# Sheet2.net
KiCad netlist of a schematic drawn in Altium Designer
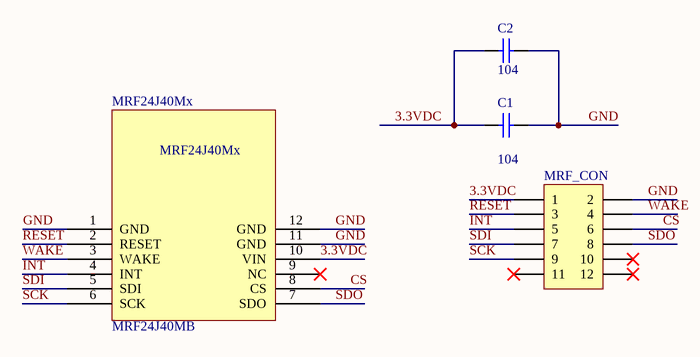
[diagram p0: Sheet2.SchDoc]

(export (version "E")
  (design (tool "Eeschema 10.0.6"))
  (components
    (comp (ref "C1")
      (value "104")
      (footprint "CN1.5")
      (description "Capacitor")
      (fields (field (name "Comment") "Cap") (field (name "PUBLISHER") "Altium Limited"))
      (libsource (lib "Miscellaneous Devices") (part "Cap"))
    )
    (comp (ref "C2")
      (value "104")
      (footprint "CN1.5")
      (description "Capacitor")
      (fields (field (name "Comment") "Cap") (field (name "PUBLISHER") "Altium Limited"))
      (libsource (lib "Miscellaneous Devices") (part "Cap"))
    )
    (comp (ref "MRF24J40Mx")
      (value "MRF24J40MB")
      (footprint "MRF24J40MB")
      (libsource (lib "syhaunguyen") (part "MRF24J40MB"))
    )
    (comp (ref "MRF_CON")
      (value "Header 6X2")
      (footprint "HDR2X6")
      (description "Header, 6-Pin, Dual row")
      (fields (field (name "PUBLISHER") "Altium Limited"))
      (libsource (lib "Miscellaneous Connectors") (part "Header 6X2"))
    )
  )
  (nets
    (net (code "1") (name "/3.3VDC") (class "Default")
      (node (ref "C1") (pin "2") (pinfunction "2_2") (pintype "passive"))
      (node (ref "C2") (pin "1") (pinfunction "1_1") (pintype "passive"))
      (node (ref "MRF24J40Mx") (pin "10") (pinfunction "VIN_10") (pintype "passive"))
      (node (ref "MRF_CON") (pin "1") (pinfunction "1_1") (pintype "passive"))
    )
    (net (code "2") (name "/CS") (class "Default")
      (node (ref "MRF24J40Mx") (pin "8") (pinfunction "CS_8") (pintype "passive"))
      (node (ref "MRF_CON") (pin "6") (pinfunction "6_6") (pintype "passive"))
    )
    (net (code "3") (name "/GND") (class "Default")
      (node (ref "C1") (pin "1") (pinfunction "1_1") (pintype "passive"))
      (node (ref "C2") (pin "2") (pinfunction "2_2") (pintype "passive"))
      (node (ref "MRF24J40Mx") (pin "1") (pinfunction "GND_1") (pintype "passive"))
      (node (ref "MRF24J40Mx") (pin "11") (pinfunction "GND_11") (pintype "passive"))
      (node (ref "MRF24J40Mx") (pin "12") (pinfunction "GND_12") (pintype "passive"))
      (node (ref "MRF_CON") (pin "2") (pinfunction "2_2") (pintype "passive"))
    )
    (net (code "4") (name "/INT") (class "Default")
      (node (ref "MRF24J40Mx") (pin "4") (pinfunction "INT_4") (pintype "passive"))
      (node (ref "MRF_CON") (pin "5") (pinfunction "5_5") (pintype "passive"))
    )
    (net (code "5") (name "/RESET") (class "Default")
      (node (ref "MRF24J40Mx") (pin "2") (pinfunction "RESET_2") (pintype "passive"))
      (node (ref "MRF_CON") (pin "3") (pinfunction "3_3") (pintype "passive"))
    )
    (net (code "6") (name "/SCK") (class "Default")
      (node (ref "MRF24J40Mx") (pin "6") (pinfunction "SCK_6") (pintype "passive"))
      (node (ref "MRF_CON") (pin "9") (pinfunction "9_9") (pintype "passive"))
    )
    (net (code "7") (name "/SDI") (class "Default")
      (node (ref "MRF24J40Mx") (pin "5") (pinfunction "SDI_5") (pintype "passive"))
      (node (ref "MRF_CON") (pin "7") (pinfunction "7_7") (pintype "passive"))
    )
    (net (code "8") (name "/SDO") (class "Default")
      (node (ref "MRF24J40Mx") (pin "7") (pinfunction "SDO_7") (pintype "passive"))
      (node (ref "MRF_CON") (pin "8") (pinfunction "8_8") (pintype "passive"))
    )
    (net (code "9") (name "/WAKE") (class "Default")
      (node (ref "MRF24J40Mx") (pin "3") (pinfunction "WAKE_3") (pintype "passive"))
      (node (ref "MRF_CON") (pin "4") (pinfunction "4_4") (pintype "passive"))
    )
    (net (code "10") (name "unconnected-(MRF24J40Mx-NC-Pad9)") (class "Default")
      (node (ref "MRF24J40Mx") (pin "9") (pinfunction "NC_9") (pintype "passive+no_connect"))
    )
    (net (code "11") (name "unconnected-(MRF_CON-Pad10)") (class "Default")
      (node (ref "MRF_CON") (pin "10") (pinfunction "10_10") (pintype "passive+no_connect"))
    )
    (net (code "12") (name "unconnected-(MRF_CON-Pad11)") (class "Default")
      (node (ref "MRF_CON") (pin "11") (pinfunction "11_11") (pintype "passive+no_connect"))
    )
    (net (code "13") (name "unconnected-(MRF_CON-Pad12)") (class "Default")
      (node (ref "MRF_CON") (pin "12") (pinfunction "12_12") (pintype "passive+no_connect"))
    )
  )
)
